# 5_Current_Sensor.net
KiCad netlist of a schematic drawn in Altium Designer
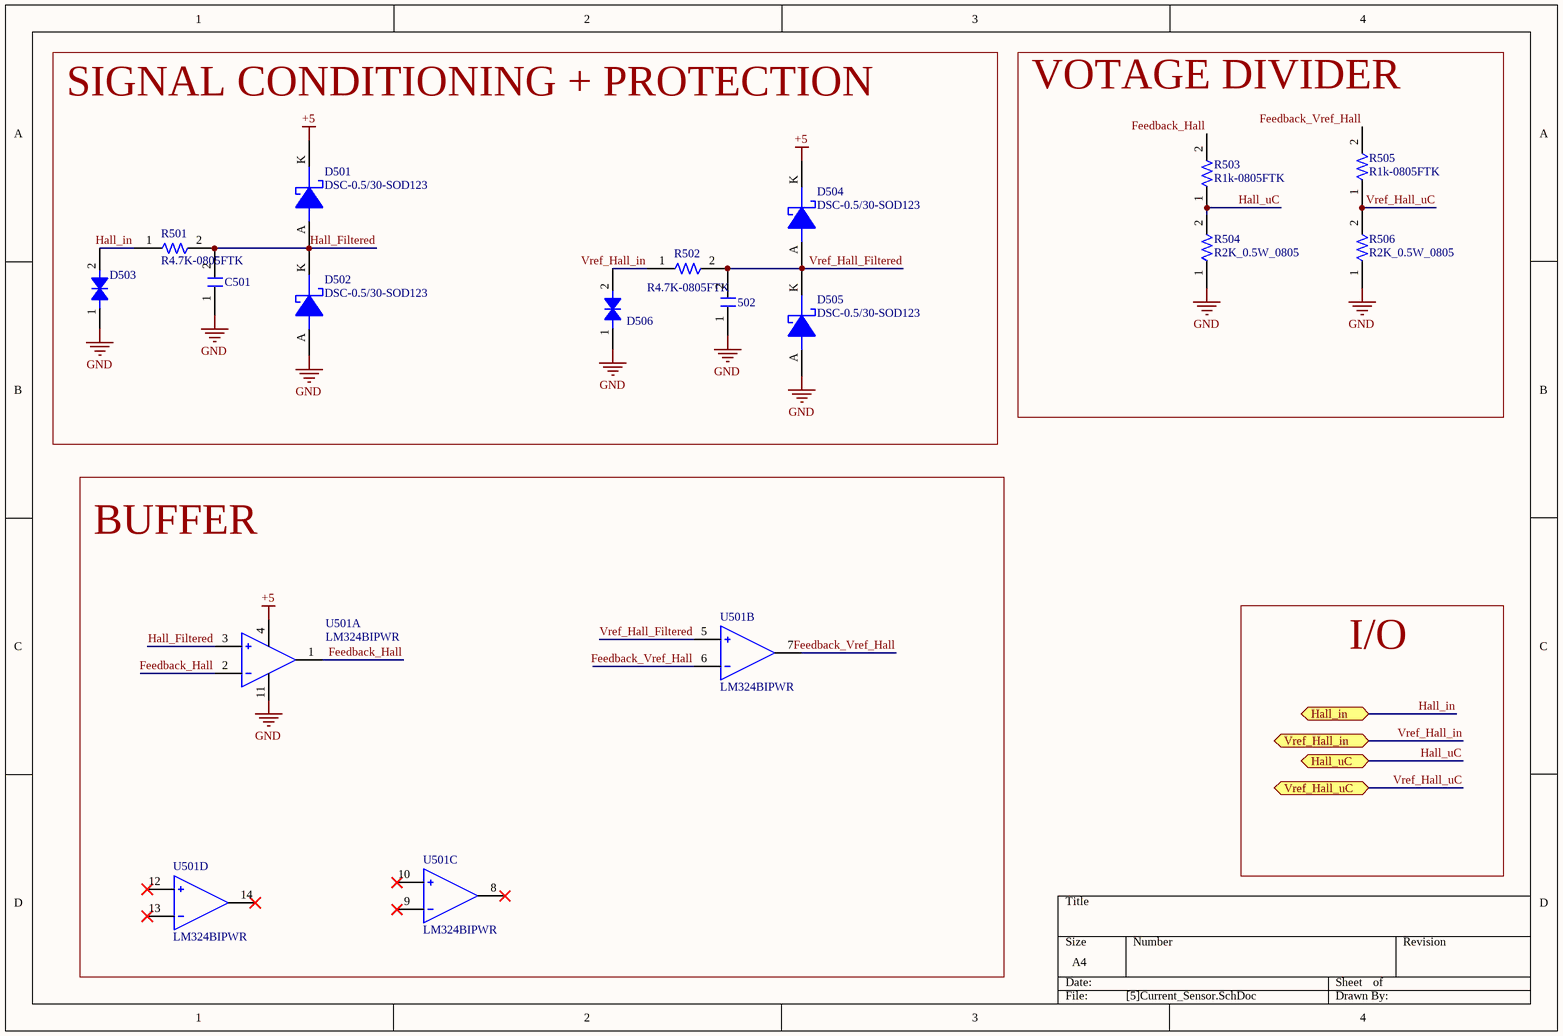
[diagram p0: [5]Current_Sensor.SchDoc]

(export (version "E")
  (design (tool "Eeschema 10.0.6"))
  (components
    (comp (ref "502")
      (value "C10n-50V-0805FNPC-X7R")
      (footprint "C0805FNPC-R")
      (description "Cap, 0.01ΜF, 50V, 10%, X7R, 0805")
      (fields (field (name "TOLERANCE") "10%") (field (name ".CREATOR") "DR"))
      (libsource (lib "EMEA- E-Tech Racing- I'Escola d'Enginyeria de Barcelona Est") (part "C100p-50V-0805FNPC-C0G/NP0"))
    )
    (comp (ref "C501")
      (value "C10n-50V-0805FNPC-X7R")
      (footprint "C0805FNPC-R")
      (description "Cap, 0.01ΜF, 50V, 10%, X7R, 0805")
      (fields (field (name "TOLERANCE") "10%") (field (name ".CREATOR") "DR"))
      (libsource (lib "EMEA- E-Tech Racing- I'Escola d'Enginyeria de Barcelona Est") (part "C100p-50V-0805FNPC-C0G/NP0"))
    )
    (comp (ref "D501")
      (value "DSC-0.5/30-SOD123")
      (footprint "DSC-SOD123")
      (description "VR=30V IF=500mA 30pF P=410mW")
      (fields (field (name ".CREATOR") "GP"))
      (libsource (lib "EMEA- E-Tech Racing- I'Escola d'Enginyeria de Barcelona Est") (part "DSC-0.5/30-SOD123"))
    )
    (comp (ref "D502")
      (value "DSC-0.5/30-SOD123")
      (footprint "DSC-SOD123")
      (description "VR=30V IF=500mA 30pF P=410mW")
      (fields (field (name ".CREATOR") "GP"))
      (libsource (lib "EMEA- E-Tech Racing- I'Escola d'Enginyeria de Barcelona Est") (part "DSC-0.5/30-SOD123"))
    )
    (comp (ref "D503")
      (value "DTVS-6V-DO-214AC")
      (footprint "DTVS-DO-214AC")
      (description "TVS diode [Würth Elektronik] 824501600 TVS diode")
      (fields
        (field (name "MANUFACTURER") "Wurth Electronics")
        (field (name "MANUFACTURER PART NUMBER") "824501600")
        (field (name ".CREATOR") "DO")
      )
      (libsource (lib "EMEA- E-Tech Racing- I'Escola d'Enginyeria de Barcelona Est") (part "DTVS-BD-30k-SOD323"))
    )
    (comp (ref "D504")
      (value "DSC-0.5/30-SOD123")
      (footprint "DSC-SOD123")
      (description "VR=30V IF=500mA 30pF P=410mW")
      (fields (field (name ".CREATOR") "GP"))
      (libsource (lib "EMEA- E-Tech Racing- I'Escola d'Enginyeria de Barcelona Est") (part "DSC-0.5/30-SOD123"))
    )
    (comp (ref "D505")
      (value "DSC-0.5/30-SOD123")
      (footprint "DSC-SOD123")
      (description "VR=30V IF=500mA 30pF P=410mW")
      (fields (field (name ".CREATOR") "GP"))
      (libsource (lib "EMEA- E-Tech Racing- I'Escola d'Enginyeria de Barcelona Est") (part "DSC-0.5/30-SOD123"))
    )
    (comp (ref "D506")
      (value "DTVS-6V-DO-214AC")
      (footprint "DTVS-DO-214AC")
      (description "TVS diode [Würth Elektronik] 824501600 TVS diode")
      (fields
        (field (name "MANUFACTURER") "Wurth Electronics")
        (field (name "MANUFACTURER PART NUMBER") "824501600")
        (field (name ".CREATOR") "DO")
      )
      (libsource (lib "EMEA- E-Tech Racing- I'Escola d'Enginyeria de Barcelona Est") (part "DTVS-BD-30k-SOD323"))
    )
    (comp (ref "R501")
      (value "R4.7K-0805FTK")
      (footprint "R0805FTK")
      (description "Res Thick Film 0805 4.7K Ohm 5% 1/8W ±200ppm/°C Molded SMD SMD Paper Tape on Plastic Reel")
      (fields (field (name "TOLERANCE") "5%") (field (name ".CREATOR") "DR"))
      (libsource (lib "EMEA- E-Tech Racing- I'Escola d'Enginyeria de Barcelona Est") (part "R9.09K-1206FTK"))
    )
    (comp (ref "R502")
      (value "R4.7K-0805FTK")
      (footprint "R0805FTK")
      (description "Res Thick Film 0805 4.7K Ohm 5% 1/8W ±200ppm/°C Molded SMD SMD Paper Tape on Plastic Reel")
      (fields (field (name "TOLERANCE") "5%") (field (name ".CREATOR") "DR"))
      (libsource (lib "EMEA- E-Tech Racing- I'Escola d'Enginyeria de Barcelona Est") (part "R9.09K-1206FTK"))
    )
    (comp (ref "R503")
      (value "R1k-0805FTK")
      (footprint "R0805FTK")
      (description "Res Thick Film 0805 1K Ohm 5% 1/8W ±200ppm/°C Molded SMD SMD Paper Tape on Plastic Reel")
      (fields (field (name "TOLERANCE") "5%") (field (name ".CREATOR") "GP"))
      (libsource (lib "EMEA- E-Tech Racing- I'Escola d'Enginyeria de Barcelona Est") (part "R9.09K-1206FTK"))
    )
    (comp (ref "R504")
      (value "R2K_0.5W_0805")
      (footprint "0805")
      (fields
        (field (name "POWER") "500mW")
        (field (name "TOLERANCE") "1%")
        (field (name "PART NUMBER") "CRCW08052K00FKEAHP")
      )
      (libsource (lib "EMEA- E-Tech Racing- I'Escola d'Enginyeria de Barcelona Est") (part "R9.09K-1206FTK"))
    )
    (comp (ref "R505")
      (value "R1k-0805FTK")
      (footprint "R0805FTK")
      (description "Res Thick Film 0805 1K Ohm 5% 1/8W ±200ppm/°C Molded SMD SMD Paper Tape on Plastic Reel")
      (fields (field (name "TOLERANCE") "5%") (field (name ".CREATOR") "GP"))
      (libsource (lib "EMEA- E-Tech Racing- I'Escola d'Enginyeria de Barcelona Est") (part "R9.09K-1206FTK"))
    )
    (comp (ref "R506")
      (value "R2K_0.5W_0805")
      (footprint "0805")
      (fields
        (field (name "POWER") "500mW")
        (field (name "TOLERANCE") "1%")
        (field (name "PART NUMBER") "CRCW08052K00FKEAHP")
      )
      (libsource (lib "EMEA- E-Tech Racing- I'Escola d'Enginyeria de Barcelona Est") (part "R9.09K-1206FTK"))
    )
    (comp (ref "U501")
      (value "LM324BIPWR")
      (footprint "FP-PW0014A-IPC_B")
      (libsource (lib "EMEA- E-Tech Racing- I'Escola d'Enginyeria de Barcelona Est") (part "OpAmp"))
    )
  )
  (nets
    (net (code "1") (name "+5") (class "Default")
      (node (ref "D501") (pin "K") (pinfunction "K_K") (pintype "passive"))
      (node (ref "D504") (pin "K") (pinfunction "K_K") (pintype "passive"))
      (node (ref "U501") (pin "4") (pinfunction "VCC+_4") (pintype "power_in"))
    )
    (net (code "2") (name "/Feedback_Hall") (class "Default")
      (node (ref "R503") (pin "2") (pinfunction "2_2") (pintype "passive"))
      (node (ref "U501") (pin "1") (pinfunction "1OUT_1") (pintype "passive"))
      (node (ref "U501") (pin "2") (pinfunction "1IN-_2") (pintype "tri_state"))
    )
    (net (code "3") (name "/Feedback_Vref_Hall") (class "Default")
      (node (ref "R505") (pin "2") (pinfunction "2_2") (pintype "passive"))
      (node (ref "U501") (pin "6") (pinfunction "2IN-_6") (pintype "tri_state"))
      (node (ref "U501") (pin "7") (pinfunction "2OUT_7") (pintype "passive"))
    )
    (net (code "4") (name "/Hall_Filtered") (class "Default")
      (node (ref "C501") (pin "2") (pinfunction "2_2") (pintype "passive"))
      (node (ref "D501") (pin "A") (pinfunction "A_A") (pintype "passive"))
      (node (ref "D502") (pin "K") (pinfunction "K_K") (pintype "passive"))
      (node (ref "R501") (pin "2") (pinfunction "2_2") (pintype "passive"))
      (node (ref "U501") (pin "3") (pinfunction "1IN+_3") (pintype "tri_state"))
    )
    (net (code "5") (name "/Hall_in") (class "Default")
      (node (ref "D503") (pin "2") (pinfunction "2_2") (pintype "passive"))
      (node (ref "R501") (pin "1") (pinfunction "1_1") (pintype "passive"))
    )
    (net (code "6") (name "/Hall_uC") (class "Default")
      (node (ref "R503") (pin "1") (pinfunction "1_1") (pintype "passive"))
      (node (ref "R504") (pin "2") (pinfunction "2_2") (pintype "passive"))
    )
    (net (code "7") (name "/Vref_Hall_Filtered") (class "Default")
      (node (ref "502") (pin "2") (pinfunction "2_2") (pintype "passive"))
      (node (ref "D504") (pin "A") (pinfunction "A_A") (pintype "passive"))
      (node (ref "D505") (pin "K") (pinfunction "K_K") (pintype "passive"))
      (node (ref "R502") (pin "2") (pinfunction "2_2") (pintype "passive"))
      (node (ref "U501") (pin "5") (pinfunction "2IN+_5") (pintype "tri_state"))
    )
    (net (code "8") (name "/Vref_Hall_in") (class "Default")
      (node (ref "D506") (pin "2") (pinfunction "2_2") (pintype "passive"))
      (node (ref "R502") (pin "1") (pinfunction "1_1") (pintype "passive"))
    )
    (net (code "9") (name "/Vref_Hall_uC") (class "Default")
      (node (ref "R505") (pin "1") (pinfunction "1_1") (pintype "passive"))
      (node (ref "R506") (pin "2") (pinfunction "2_2") (pintype "passive"))
    )
    (net (code "10") (name "GND") (class "Default")
      (node (ref "502") (pin "1") (pinfunction "1_1") (pintype "passive"))
      (node (ref "C501") (pin "1") (pinfunction "1_1") (pintype "passive"))
      (node (ref "D502") (pin "A") (pinfunction "A_A") (pintype "passive"))
      (node (ref "D503") (pin "1") (pinfunction "1_1") (pintype "passive"))
      (node (ref "D505") (pin "A") (pinfunction "A_A") (pintype "passive"))
      (node (ref "D506") (pin "1") (pinfunction "1_1") (pintype "passive"))
      (node (ref "R504") (pin "1") (pinfunction "1_1") (pintype "passive"))
      (node (ref "R506") (pin "1") (pinfunction "1_1") (pintype "passive"))
      (node (ref "U501") (pin "11") (pinfunction "VCC-_11") (pintype "power_in"))
    )
    (net (code "11") (name "unconnected-(U501C-3IN+-Pad10)") (class "Default")
      (node (ref "U501") (pin "10") (pinfunction "3IN+_10") (pintype "tri_state+no_connect"))
    )
    (net (code "12") (name "unconnected-(U501C-3IN--Pad9)") (class "Default")
      (node (ref "U501") (pin "9") (pinfunction "3IN-_9") (pintype "tri_state+no_connect"))
    )
    (net (code "13") (name "unconnected-(U501C-3OUT-Pad8)") (class "Default")
      (node (ref "U501") (pin "8") (pinfunction "3OUT_8") (pintype "passive+no_connect"))
    )
    (net (code "14") (name "unconnected-(U501D-4IN+-Pad12)") (class "Default")
      (node (ref "U501") (pin "12") (pinfunction "4IN+_12") (pintype "tri_state+no_connect"))
    )
    (net (code "15") (name "unconnected-(U501D-4IN--Pad13)") (class "Default")
      (node (ref "U501") (pin "13") (pinfunction "4IN-_13") (pintype "tri_state+no_connect"))
    )
    (net (code "16") (name "unconnected-(U501D-4OUT-Pad14)") (class "Default")
      (node (ref "U501") (pin "14") (pinfunction "4OUT_14") (pintype "passive+no_connect"))
    )
  )
)
